# hall_effect_module.net
KiCad netlist of a schematic drawn in Altium Designer
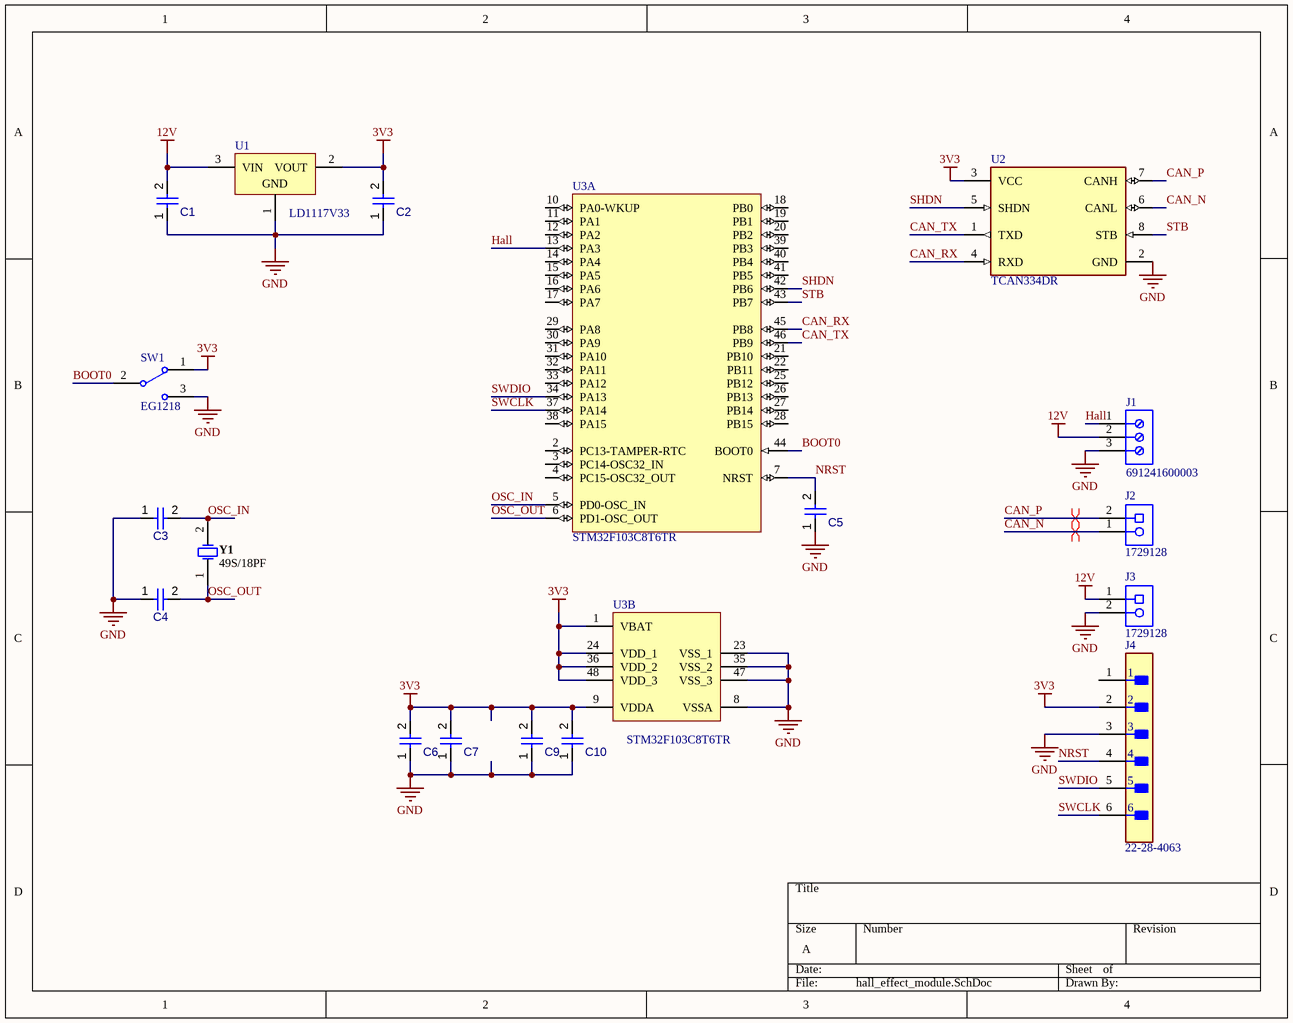
[diagram p0: hall_effect_module.SchDoc]

(export (version "E")
  (design (tool "Eeschema 10.0.6"))
  (components
    (comp (ref "C1")
      (value "Capacitor 100nF +/-20% 25V 0402")
      (footprint "CAPC0402(1005)60_L")
      (description "Chip Capacitor, 100nF +/-20%, 25V, 0402, Thickness 0.6 mm")
      (fields (field (name "TOLERANCE") "10%"))
      (libsource (lib "Marcus Bettencourt") (part "CAP-NP-2"))
    )
    (comp (ref "C2")
      (value "Capacitor 10 uF +/- 10% 16 V 0805")
      (footprint "CAPC2013X135X45NL10T25")
      (description "Chip Capacitor, 10 uF, +/- 10%, 16 V, 0805 (2012 Metric)")
      (fields (field (name "TOLERANCE") "10%"))
      (libsource (lib "Marcus Bettencourt") (part "CAP-NP-2"))
    )
    (comp (ref "C3")
      (value "Capacitor 22pF +/-10% 50V 0402")
      (footprint "CAPC0402(1005)60_L")
      (description "Chip Capacitor, 22pF +/-10%, 50V, 0402, Thickness 0.6 mm")
      (fields (field (name "TOLERANCE") "10%"))
      (libsource (lib "Marcus Bettencourt") (part "CAP-NP-2"))
    )
    (comp (ref "C4")
      (value "Capacitor 22pF +/-10% 50V 0402")
      (footprint "CAPC0402(1005)60_L")
      (description "Chip Capacitor, 22pF +/-10%, 50V, 0402, Thickness 0.6 mm")
      (fields (field (name "TOLERANCE") "10%"))
      (libsource (lib "Marcus Bettencourt") (part "CAP-NP-2"))
    )
    (comp (ref "C5")
      (value "Capacitor 100 nF +/-10% 50 V 0805")
      (footprint "CAPC2013X95X50LL10T25")
      (description "Chip Capacitor, 100 nF, +/- 10%, 50 V, 0805 (2012 Metric)")
      (fields (field (name "TOLERANCE") "10%"))
      (libsource (lib "Marcus Bettencourt") (part "CAP-NP-2"))
    )
    (comp (ref "C6")
      (value "Capacitor 100 nF +/-10% 50 V 0805")
      (footprint "CAPC2013X95X50LL10T25")
      (description "Chip Capacitor, 100 nF, +/- 10%, 50 V, 0805 (2012 Metric)")
      (fields (field (name "TOLERANCE") "10%"))
      (libsource (lib "Marcus Bettencourt") (part "CAP-NP-2"))
    )
    (comp (ref "C7")
      (value "Capacitor 100 nF +/-10% 50 V 0805")
      (footprint "CAPC2013X95X50LL10T25")
      (description "Chip Capacitor, 100 nF, +/- 10%, 50 V, 0805 (2012 Metric)")
      (fields (field (name "TOLERANCE") "10%"))
      (libsource (lib "Marcus Bettencourt") (part "CAP-NP-2"))
    )
    (comp (ref "C9")
      (value "Capacitor 100 nF +/-10% 50 V 0805")
      (footprint "CAPC2013X95X50LL10T25")
      (description "Chip Capacitor, 100 nF, +/- 10%, 50 V, 0805 (2012 Metric)")
      (fields (field (name "TOLERANCE") "10%"))
      (libsource (lib "Marcus Bettencourt") (part "CAP-NP-2"))
    )
    (comp (ref "C10")
      (value "Capacitor 100 nF +/-10% 50 V 0805")
      (footprint "CAPC2013X95X50LL10T25")
      (description "Chip Capacitor, 100 nF, +/- 10%, 50 V, 0805 (2012 Metric)")
      (fields (field (name "TOLERANCE") "10%"))
      (libsource (lib "Marcus Bettencourt") (part "CAP-NP-2"))
    )
    (comp (ref "J1")
      (value "691241600003")
      (footprint "691241600003")
      (description "Terminal Block, 10.16MM Pitch, Vertical, Rising Cage Clamp, 14-30 AWG, 3 Pin")
      (libsource (lib "Altium Content Vault") (part "TBL - 1R - 03P - Screw"))
    )
    (comp (ref "J2")
      (value "1729128")
      (footprint "PHOE-1729128-2_V")
      (description "PCB Terminal Block, 13.5 A, 400 V, 2-Pin THD, RoHS, Bulk")
      (fields (field (name "MANUFACTURER") "Phoenix Contact"))
      (libsource (lib "Altium Content Vault") (part "CN-2P-F-R2"))
    )
    (comp (ref "J3")
      (value "1729128")
      (footprint "PHOE-1729128-2_V")
      (description "PCB Terminal Block, 13.5 A, 400 V, 2-Pin THD, RoHS, Bulk")
      (fields (field (name "MANUFACTURER") "Phoenix Contact"))
      (libsource (lib "") (part "CN-2P-F-R2_1"))
    )
    (comp (ref "J4")
      (value "22-28-4063")
      (footprint "FP-22-28-4063-MFG")
      (description "CONN HEADER VERT 6POS 2.54MM")
      (libsource (lib "Altium Content Vault") (part "f2cb566baf1c37ab5a3b8e90bbeafd6"))
    )
    (comp (ref "SW1")
      (value "EG1218")
      (footprint "ESWI-EG1218_V")
      (description "Slide Switch, SPDT, 500 V, -20 to 70 degC, 3-Pin THD, RoHS, Bulk")
      (fields (field (name "MANUFACTURER") "E-Switch"))
      (libsource (lib "Marcus Bettencourt") (part "SW-SPDT-3_B"))
    )
    (comp (ref "U1")
      (value "LD1117V33")
      (footprint "STM-TO220-3")
      (fields (field (name "MANUFACTURER") "STMicroelectronics") (field (name "POWER") "12W"))
      (libsource (lib "Marcus Bettencourt") (part "STM-LD1117-V33"))
    )
    (comp (ref "U2")
      (value "TCAN334DR")
      (footprint "FP-D0008A-IPC_B")
      (description "IC TRANSCEIVER 1/1 8SOIC")
      (libsource (lib "Altium Content Vault") (part "c7894c070e2c479120e8bad9558e918"))
    )
    (comp (ref "U3")
      (value "STM32F103C8T6TR")
      (footprint "STM-LQFP48_M")
      (libsource (lib "Altium Content Vault") (part "MC-ARM-STM32F103X8_B-SQ48"))
    )
    (comp (ref "Y1")
      (value "49S/18PF")
      (footprint "JPY-49S-18PF")
      (description "Crystal, 16 MHz, +/-20 ppm, 18 pF, -20 to 70 degC, 2-Pin THD, RoHS")
      (fields (field (name "MANUFACTURER") "Shenzhen Jingpengyuan"))
      (libsource (lib "Marcus Bettencourt") (part "XTAL-1-2-2"))
    )
  )
  (nets
    (net (code "1") (name "/BOOT0") (class "Default")
      (node (ref "SW1") (pin "2") (pinfunction "COM_2") (pintype "passive"))
      (node (ref "U3") (pin "44") (pinfunction "BOOT0_44") (pintype "input"))
    )
    (net (code "2") (name "/CAN_N") (class "Default")
      (node (ref "J2") (pin "1") (pinfunction "1_1") (pintype "passive"))
      (node (ref "U2") (pin "6") (pinfunction "CANL_6") (pintype "bidirectional"))
    )
    (net (code "3") (name "/CAN_P") (class "Default")
      (node (ref "J2") (pin "2") (pinfunction "2_2") (pintype "passive"))
      (node (ref "U2") (pin "7") (pinfunction "CANH_7") (pintype "bidirectional"))
    )
    (net (code "4") (name "/CAN_RX") (class "Default")
      (node (ref "U2") (pin "4") (pinfunction "RXD_4") (pintype "input"))
      (node (ref "U3") (pin "45") (pinfunction "PB8_45") (pintype "bidirectional"))
    )
    (net (code "5") (name "/CAN_TX") (class "Default")
      (node (ref "U2") (pin "1") (pinfunction "TXD_1") (pintype "output"))
      (node (ref "U3") (pin "46") (pinfunction "PB9_46") (pintype "bidirectional"))
    )
    (net (code "6") (name "/Hall") (class "Default")
      (node (ref "J1") (pin "1") (pinfunction "1_1") (pintype "passive"))
      (node (ref "U3") (pin "13") (pinfunction "PA3_13") (pintype "bidirectional"))
    )
    (net (code "7") (name "/NRST") (class "Default")
      (node (ref "C5") (pin "2") (pinfunction "2_2") (pintype "passive"))
      (node (ref "J4") (pin "4") (pinfunction "4_4") (pintype "passive"))
      (node (ref "U3") (pin "7") (pinfunction "NRST_7") (pintype "bidirectional"))
    )
    (net (code "8") (name "/OSC_IN") (class "Default")
      (node (ref "C3") (pin "2") (pinfunction "2_2") (pintype "passive"))
      (node (ref "U3") (pin "5") (pinfunction "PD0-OSC_IN_5") (pintype "bidirectional"))
      (node (ref "Y1") (pin "2") (pinfunction "2_2") (pintype "passive"))
    )
    (net (code "9") (name "/OSC_OUT") (class "Default")
      (node (ref "C4") (pin "2") (pinfunction "2_2") (pintype "passive"))
      (node (ref "U3") (pin "6") (pinfunction "PD1-OSC_OUT_6") (pintype "bidirectional"))
      (node (ref "Y1") (pin "1") (pinfunction "1_1") (pintype "passive"))
    )
    (net (code "10") (name "/SHDN") (class "Default")
      (node (ref "U2") (pin "5") (pinfunction "SHDN_5") (pintype "input"))
      (node (ref "U3") (pin "42") (pinfunction "PB6_42") (pintype "bidirectional"))
    )
    (net (code "11") (name "/STB") (class "Default")
      (node (ref "U2") (pin "8") (pinfunction "STB_8") (pintype "input"))
      (node (ref "U3") (pin "43") (pinfunction "PB7_43") (pintype "bidirectional"))
    )
    (net (code "12") (name "/SWCLK") (class "Default")
      (node (ref "J4") (pin "6") (pinfunction "6_6") (pintype "passive"))
      (node (ref "U3") (pin "37") (pinfunction "PA14_37") (pintype "bidirectional"))
    )
    (net (code "13") (name "/SWDIO") (class "Default")
      (node (ref "J4") (pin "5") (pinfunction "5_5") (pintype "passive"))
      (node (ref "U3") (pin "34") (pinfunction "PA13_34") (pintype "bidirectional"))
    )
    (net (code "14") (name "3V3") (class "Default")
      (node (ref "C10") (pin "2") (pinfunction "2_2") (pintype "passive"))
      (node (ref "C2") (pin "2") (pinfunction "2_2") (pintype "passive"))
      (node (ref "C6") (pin "2") (pinfunction "2_2") (pintype "passive"))
      (node (ref "C7") (pin "2") (pinfunction "2_2") (pintype "passive"))
      (node (ref "C9") (pin "2") (pinfunction "2_2") (pintype "passive"))
      (node (ref "J4") (pin "2") (pinfunction "2_2") (pintype "passive"))
      (node (ref "SW1") (pin "1") (pinfunction "1_1") (pintype "passive"))
      (node (ref "U1") (pin "2") (pinfunction "VOUT_2") (pintype "power_in"))
      (node (ref "U2") (pin "3") (pinfunction "VCC_3") (pintype "power_in"))
      (node (ref "U3") (pin "1") (pinfunction "VBAT_1") (pintype "power_in"))
      (node (ref "U3") (pin "24") (pinfunction "VDD_1_24") (pintype "power_in"))
      (node (ref "U3") (pin "36") (pinfunction "VDD_2_36") (pintype "power_in"))
      (node (ref "U3") (pin "48") (pinfunction "VDD_3_48") (pintype "power_in"))
      (node (ref "U3") (pin "9") (pinfunction "VDDA_9") (pintype "power_in"))
    )
    (net (code "15") (name "12V") (class "Default")
      (node (ref "C1") (pin "2") (pinfunction "2_2") (pintype "passive"))
      (node (ref "J1") (pin "2") (pinfunction "2_2") (pintype "passive"))
      (node (ref "J3") (pin "1") (pinfunction "1_1") (pintype "passive"))
      (node (ref "U1") (pin "3") (pinfunction "VIN_3") (pintype "power_in"))
    )
    (net (code "16") (name "GND") (class "Default")
      (node (ref "C1") (pin "1") (pinfunction "1_1") (pintype "passive"))
      (node (ref "C10") (pin "1") (pinfunction "1_1") (pintype "passive"))
      (node (ref "C2") (pin "1") (pinfunction "1_1") (pintype "passive"))
      (node (ref "C3") (pin "1") (pinfunction "1_1") (pintype "passive"))
      (node (ref "C4") (pin "1") (pinfunction "1_1") (pintype "passive"))
      (node (ref "C5") (pin "1") (pinfunction "1_1") (pintype "passive"))
      (node (ref "C6") (pin "1") (pinfunction "1_1") (pintype "passive"))
      (node (ref "C7") (pin "1") (pinfunction "1_1") (pintype "passive"))
      (node (ref "C9") (pin "1") (pinfunction "1_1") (pintype "passive"))
      (node (ref "J1") (pin "3") (pinfunction "3_3") (pintype "passive"))
      (node (ref "J3") (pin "2") (pinfunction "2_2") (pintype "passive"))
      (node (ref "J4") (pin "3") (pinfunction "3_3") (pintype "passive"))
      (node (ref "SW1") (pin "3") (pinfunction "3_3") (pintype "passive"))
      (node (ref "U1") (pin "1") (pinfunction "GND_1") (pintype "power_in"))
      (node (ref "U2") (pin "2") (pinfunction "GND_2") (pintype "power_in"))
      (node (ref "U3") (pin "23") (pinfunction "VSS_1_23") (pintype "power_in"))
      (node (ref "U3") (pin "35") (pinfunction "VSS_2_35") (pintype "power_in"))
      (node (ref "U3") (pin "47") (pinfunction "VSS_3_47") (pintype "power_in"))
      (node (ref "U3") (pin "8") (pinfunction "VSSA_8") (pintype "power_in"))
    )
    (net (code "17") (name "unconnected-(J4-Pad1)") (class "Default")
      (node (ref "J4") (pin "1") (pinfunction "1_1") (pintype "passive"))
    )
    (net (code "18") (name "unconnected-(U3A-PA0-WKUP-Pad10)") (class "Default")
      (node (ref "U3") (pin "10") (pinfunction "PA0-WKUP_10") (pintype "bidirectional"))
    )
    (net (code "19") (name "unconnected-(U3A-PA1-Pad11)") (class "Default")
      (node (ref "U3") (pin "11") (pinfunction "PA1_11") (pintype "bidirectional"))
    )
    (net (code "20") (name "unconnected-(U3A-PA2-Pad12)") (class "Default")
      (node (ref "U3") (pin "12") (pinfunction "PA2_12") (pintype "bidirectional"))
    )
    (net (code "21") (name "unconnected-(U3A-PA4-Pad14)") (class "Default")
      (node (ref "U3") (pin "14") (pinfunction "PA4_14") (pintype "bidirectional"))
    )
    (net (code "22") (name "unconnected-(U3A-PA5-Pad15)") (class "Default")
      (node (ref "U3") (pin "15") (pinfunction "PA5_15") (pintype "bidirectional"))
    )
    (net (code "23") (name "unconnected-(U3A-PA6-Pad16)") (class "Default")
      (node (ref "U3") (pin "16") (pinfunction "PA6_16") (pintype "bidirectional"))
    )
    (net (code "24") (name "unconnected-(U3A-PA7-Pad17)") (class "Default")
      (node (ref "U3") (pin "17") (pinfunction "PA7_17") (pintype "bidirectional"))
    )
    (net (code "25") (name "unconnected-(U3A-PA8-Pad29)") (class "Default")
      (node (ref "U3") (pin "29") (pinfunction "PA8_29") (pintype "bidirectional"))
    )
    (net (code "26") (name "unconnected-(U3A-PA9-Pad30)") (class "Default")
      (node (ref "U3") (pin "30") (pinfunction "PA9_30") (pintype "bidirectional"))
    )
    (net (code "27") (name "unconnected-(U3A-PA10-Pad31)") (class "Default")
      (node (ref "U3") (pin "31") (pinfunction "PA10_31") (pintype "bidirectional"))
    )
    (net (code "28") (name "unconnected-(U3A-PA11-Pad32)") (class "Default")
      (node (ref "U3") (pin "32") (pinfunction "PA11_32") (pintype "bidirectional"))
    )
    (net (code "29") (name "unconnected-(U3A-PA12-Pad33)") (class "Default")
      (node (ref "U3") (pin "33") (pinfunction "PA12_33") (pintype "bidirectional"))
    )
    (net (code "30") (name "unconnected-(U3A-PA15-Pad38)") (class "Default")
      (node (ref "U3") (pin "38") (pinfunction "PA15_38") (pintype "bidirectional"))
    )
    (net (code "31") (name "unconnected-(U3A-PB0-Pad18)") (class "Default")
      (node (ref "U3") (pin "18") (pinfunction "PB0_18") (pintype "bidirectional"))
    )
    (net (code "32") (name "unconnected-(U3A-PB1-Pad19)") (class "Default")
      (node (ref "U3") (pin "19") (pinfunction "PB1_19") (pintype "bidirectional"))
    )
    (net (code "33") (name "unconnected-(U3A-PB2-Pad20)") (class "Default")
      (node (ref "U3") (pin "20") (pinfunction "PB2_20") (pintype "bidirectional"))
    )
    (net (code "34") (name "unconnected-(U3A-PB3-Pad39)") (class "Default")
      (node (ref "U3") (pin "39") (pinfunction "PB3_39") (pintype "bidirectional"))
    )
    (net (code "35") (name "unconnected-(U3A-PB4-Pad40)") (class "Default")
      (node (ref "U3") (pin "40") (pinfunction "PB4_40") (pintype "bidirectional"))
    )
    (net (code "36") (name "unconnected-(U3A-PB5-Pad41)") (class "Default")
      (node (ref "U3") (pin "41") (pinfunction "PB5_41") (pintype "bidirectional"))
    )
    (net (code "37") (name "unconnected-(U3A-PB10-Pad21)") (class "Default")
      (node (ref "U3") (pin "21") (pinfunction "PB10_21") (pintype "bidirectional"))
    )
    (net (code "38") (name "unconnected-(U3A-PB11-Pad22)") (class "Default")
      (node (ref "U3") (pin "22") (pinfunction "PB11_22") (pintype "bidirectional"))
    )
    (net (code "39") (name "unconnected-(U3A-PB12-Pad25)") (class "Default")
      (node (ref "U3") (pin "25") (pinfunction "PB12_25") (pintype "bidirectional"))
    )
    (net (code "40") (name "unconnected-(U3A-PB13-Pad26)") (class "Default")
      (node (ref "U3") (pin "26") (pinfunction "PB13_26") (pintype "bidirectional"))
    )
    (net (code "41") (name "unconnected-(U3A-PB14-Pad27)") (class "Default")
      (node (ref "U3") (pin "27") (pinfunction "PB14_27") (pintype "bidirectional"))
    )
    (net (code "42") (name "unconnected-(U3A-PB15-Pad28)") (class "Default")
      (node (ref "U3") (pin "28") (pinfunction "PB15_28") (pintype "bidirectional"))
    )
    (net (code "43") (name "unconnected-(U3A-PC13-TAMPER-RTC-Pad2)") (class "Default")
      (node (ref "U3") (pin "2") (pinfunction "PC13-TAMPER-RTC_2") (pintype "bidirectional"))
    )
    (net (code "44") (name "unconnected-(U3A-PC14-OSC32_IN-Pad3)") (class "Default")
      (node (ref "U3") (pin "3") (pinfunction "PC14-OSC32_IN_3") (pintype "bidirectional"))
    )
    (net (code "45") (name "unconnected-(U3A-PC15-OSC32_OUT-Pad4)") (class "Default")
      (node (ref "U3") (pin "4") (pinfunction "PC15-OSC32_OUT_4") (pintype "bidirectional"))
    )
  )
)
